# ejection.net
KiCad netlist of a schematic drawn in Altium Designer
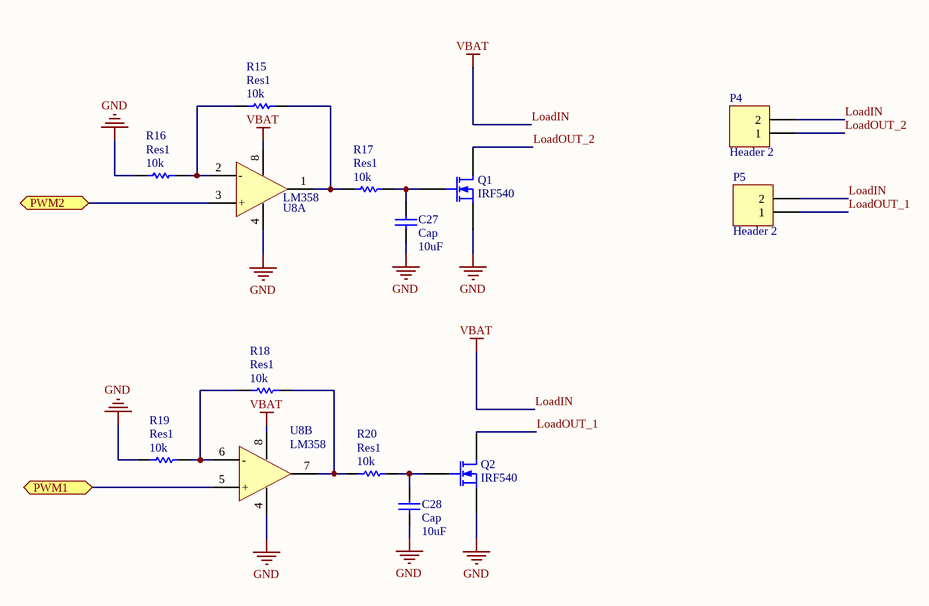
[diagram p0: ejection.SchDoc]

(export (version "E")
  (design (tool "Eeschema 10.0.6"))
  (components
    (comp (ref "C27")
      (value "Cap")
      (footprint "0805-CAP")
      (description "Capacitor")
      (fields (field (name "ALTIUM_VALUE") "10uF") (field (name "PUBLISHER") "Altium Limited"))
      (libsource (lib "Miscellaneous Devices") (part "Cap"))
    )
    (comp (ref "C28")
      (value "Cap")
      (footprint "0805-CAP")
      (description "Capacitor")
      (fields (field (name "ALTIUM_VALUE") "10uF") (field (name "PUBLISHER") "Altium Limited"))
      (libsource (lib "Miscellaneous Devices") (part "Cap"))
    )
    (comp (ref "P4")
      (value "Header 2")
      (footprint "Battery 2")
      (description "Header, 2-Pin")
      (fields (field (name "PUBLISHER") "Altium Limited"))
      (libsource (lib "Miscellaneous Connectors") (part "Header 2"))
    )
    (comp (ref "P5")
      (value "Header 2")
      (footprint "Battery 2")
      (description "Header, 2-Pin")
      (fields (field (name "PUBLISHER") "Altium Limited"))
      (libsource (lib "Miscellaneous Connectors") (part "Header 2"))
    )
    (comp (ref "Q1")
      (value "IRF540")
      (footprint "TO-263-AA")
      (description "N-Channel MOSFET")
      (fields (field (name "PUBLISHER") "Altium Limited"))
      (libsource (lib "Miscellaneous Devices") (part "MOSFET-N"))
    )
    (comp (ref "Q2")
      (value "IRF540")
      (footprint "TO-263-AA")
      (description "N-Channel MOSFET")
      (fields (field (name "PUBLISHER") "Altium Limited"))
      (libsource (lib "Miscellaneous Devices") (part "MOSFET-N"))
    )
    (comp (ref "R15")
      (value "Res1")
      (footprint "0805-RES")
      (description "Resistor")
      (fields (field (name "ALTIUM_VALUE") "10k") (field (name "PUBLISHER") "Altium Limited"))
      (libsource (lib "Miscellaneous Devices") (part "Res1"))
    )
    (comp (ref "R16")
      (value "Res1")
      (footprint "0805-RES")
      (description "Resistor")
      (fields (field (name "ALTIUM_VALUE") "10k") (field (name "PUBLISHER") "Altium Limited"))
      (libsource (lib "Miscellaneous Devices") (part "Res1"))
    )
    (comp (ref "R17")
      (value "Res1")
      (footprint "0805-RES")
      (description "Resistor")
      (fields (field (name "ALTIUM_VALUE") "10k") (field (name "PUBLISHER") "Altium Limited"))
      (libsource (lib "Miscellaneous Devices") (part "Res1"))
    )
    (comp (ref "R18")
      (value "Res1")
      (footprint "0805-RES")
      (description "Resistor")
      (fields (field (name "ALTIUM_VALUE") "10k") (field (name "PUBLISHER") "Altium Limited"))
      (libsource (lib "Miscellaneous Devices") (part "Res1"))
    )
    (comp (ref "R19")
      (value "Res1")
      (footprint "0805-RES")
      (description "Resistor")
      (fields (field (name "ALTIUM_VALUE") "10k") (field (name "PUBLISHER") "Altium Limited"))
      (libsource (lib "Miscellaneous Devices") (part "Res1"))
    )
    (comp (ref "R20")
      (value "Res1")
      (footprint "0805-RES")
      (description "Resistor")
      (fields (field (name "ALTIUM_VALUE") "10k") (field (name "PUBLISHER") "Altium Limited"))
      (libsource (lib "Miscellaneous Devices") (part "Res1"))
    )
    (comp (ref "U8")
      (value "LM358")
      (footprint "SOIC-8")
      (description "LM358 OPAMP")
      (libsource (lib "") (part "LM358_1"))
    )
  )
  (nets
    (net (code "1") (name "/LoadOUT_1") (class "Default")
      (node (ref "P5") (pin "1") (pinfunction "1_1") (pintype "passive"))
      (node (ref "Q2") (pin "1") (pinfunction "D_1") (pintype "passive"))
    )
    (net (code "2") (name "/LoadOUT_2") (class "Default")
      (node (ref "P4") (pin "1") (pinfunction "1_1") (pintype "passive"))
      (node (ref "Q1") (pin "1") (pinfunction "D_1") (pintype "passive"))
    )
    (net (code "3") (name "/PWM1") (class "Default")
      (node (ref "U8") (pin "5") (pinfunction "+_5") (pintype "passive"))
    )
    (net (code "4") (name "/PWM2") (class "Default")
      (node (ref "U8") (pin "3") (pinfunction "+_3") (pintype "passive"))
    )
    (net (code "5") (name "GND") (class "Default")
      (node (ref "C27") (pin "1") (pinfunction "1_1") (pintype "passive"))
      (node (ref "C28") (pin "1") (pinfunction "1_1") (pintype "passive"))
      (node (ref "Q1") (pin "3") (pinfunction "S_3") (pintype "passive"))
      (node (ref "Q2") (pin "3") (pinfunction "S_3") (pintype "passive"))
      (node (ref "R16") (pin "1") (pinfunction "1_1") (pintype "passive"))
      (node (ref "R19") (pin "1") (pinfunction "1_1") (pintype "passive"))
      (node (ref "U8") (pin "4") (pinfunction "VCC-_4") (pintype "passive"))
    )
    (net (code "6") (name "Net-(Q1-G)") (class "Default")
      (node (ref "C27") (pin "2") (pinfunction "2_2") (pintype "passive"))
      (node (ref "Q1") (pin "2") (pinfunction "G_2") (pintype "passive"))
      (node (ref "R17") (pin "2") (pinfunction "2_2") (pintype "passive"))
    )
    (net (code "7") (name "Net-(Q2-G)") (class "Default")
      (node (ref "C28") (pin "2") (pinfunction "2_2") (pintype "passive"))
      (node (ref "Q2") (pin "2") (pinfunction "G_2") (pintype "passive"))
      (node (ref "R20") (pin "2") (pinfunction "2_2") (pintype "passive"))
    )
    (net (code "8") (name "Net-(U8A--)") (class "Default")
      (node (ref "R15") (pin "1") (pinfunction "1_1") (pintype "passive"))
      (node (ref "R16") (pin "2") (pinfunction "2_2") (pintype "passive"))
      (node (ref "U8") (pin "2") (pinfunction "-_2") (pintype "passive"))
    )
    (net (code "9") (name "Net-(U8A-OUT)") (class "Default")
      (node (ref "R15") (pin "2") (pinfunction "2_2") (pintype "passive"))
      (node (ref "R17") (pin "1") (pinfunction "1_1") (pintype "passive"))
      (node (ref "U8") (pin "1") (pinfunction "OUT_1") (pintype "passive"))
    )
    (net (code "10") (name "Net-(U8B--)") (class "Default")
      (node (ref "R18") (pin "1") (pinfunction "1_1") (pintype "passive"))
      (node (ref "R19") (pin "2") (pinfunction "2_2") (pintype "passive"))
      (node (ref "U8") (pin "6") (pinfunction "-_6") (pintype "passive"))
    )
    (net (code "11") (name "Net-(U8B-OUT)") (class "Default")
      (node (ref "R18") (pin "2") (pinfunction "2_2") (pintype "passive"))
      (node (ref "R20") (pin "1") (pinfunction "1_1") (pintype "passive"))
      (node (ref "U8") (pin "7") (pinfunction "OUT_7") (pintype "passive"))
    )
    (net (code "12") (name "VBAT") (class "Default")
      (node (ref "P4") (pin "2") (pinfunction "2_2") (pintype "passive"))
      (node (ref "P5") (pin "2") (pinfunction "2_2") (pintype "passive"))
      (node (ref "U8") (pin "8") (pinfunction "VCC+_8") (pintype "passive"))
    )
  )
)
